# MotorControl-v1.net
KiCad netlist of a schematic drawn in EAGLE
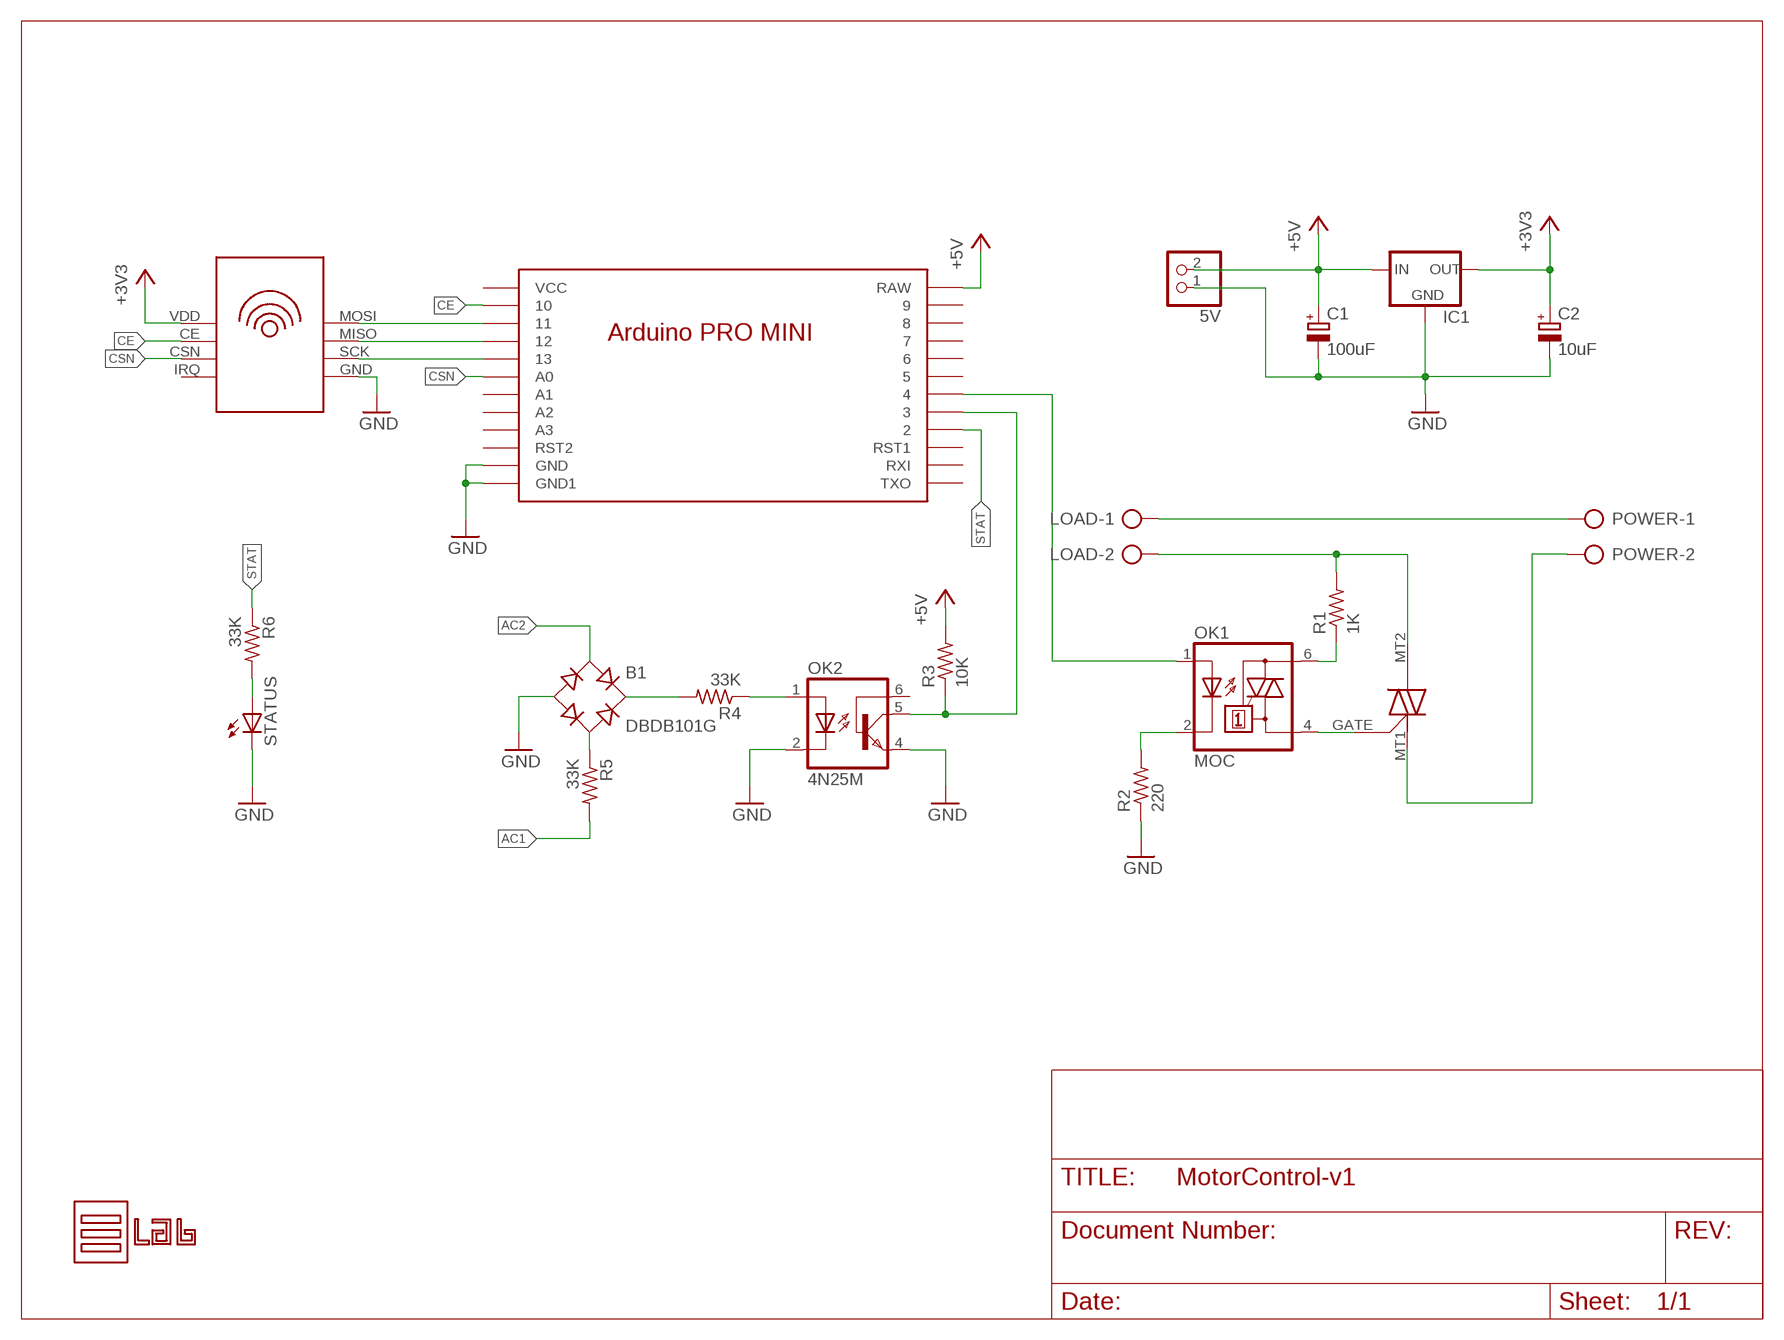
[diagram p0: schematic, sheet 1]

(export (version "E")
  (design (tool "Eeschema 10.0.6"))
  (components
    (comp (ref "5V")
      (value "PINHD-1X2")
      (footprint "eagle-import:1X02")
      (libsource (lib "eagle-import") (part "PINHD-1X2"))
    )
    (comp (ref "B1")
      (value "DBDB101G")
      (footprint "eagle-import:DB")
      (libsource (lib "eagle-import") (part "DB?GDB101"))
    )
    (comp (ref "C1")
      (value "100uF")
      (footprint "eagle-import:E2-5")
      (libsource (lib "eagle-import") (part "CPOL-EUE2-5"))
    )
    (comp (ref "C2")
      (value "10uF")
      (footprint "eagle-import:E2-5")
      (libsource (lib "eagle-import") (part "CPOL-EUE2-5"))
    )
    (comp (ref "IC1")
      (value "78LXX")
      (footprint "eagle-import:78LXX")
      (libsource (lib "eagle-import") (part "78LXX"))
    )
    (comp (ref "J1")
      (value "MAC12")
      (footprint "eagle-import:MAC12")
      (libsource (lib "eagle-import") (part "MAC12"))
    )
    (comp (ref "LOAD")
      (value "AK300/2")
      (footprint "eagle-import:AK300_2")
      (libsource (lib "eagle-import") (part "AK300/2"))
    )
    (comp (ref "OK1")
      (value "MOC")
      (footprint "eagle-import:DIL06")
      (fields (field (name "MF") "FAIRCHILD SEMICONDUCTOR") (field (name "MPN") "MOC3041M"))
      (libsource (lib "eagle-import") (part "MOC3041M"))
    )
    (comp (ref "OK2")
      (value "4N25M")
      (footprint "eagle-import:DIL06")
      (fields (field (name "MPN") "4N25-M"))
      (libsource (lib "eagle-import") (part "4N?M25"))
    )
    (comp (ref "POWER")
      (value "AK300/2")
      (footprint "eagle-import:AK300_2")
      (libsource (lib "eagle-import") (part "AK300/2"))
    )
    (comp (ref "R1")
      (value "1K")
      (footprint "eagle-import:0204_7")
      (libsource (lib "eagle-import") (part "R-US_0204/7"))
    )
    (comp (ref "R2")
      (value "220")
      (footprint "eagle-import:0204_7")
      (libsource (lib "eagle-import") (part "R-US_0204/7"))
    )
    (comp (ref "R3")
      (value "10K")
      (footprint "eagle-import:0204_7")
      (libsource (lib "eagle-import") (part "R-US_0204/7"))
    )
    (comp (ref "R4")
      (value "33K")
      (footprint "eagle-import:0204_7")
      (libsource (lib "eagle-import") (part "R-US_0204/7"))
    )
    (comp (ref "R5")
      (value "33K")
      (footprint "eagle-import:0204_7")
      (libsource (lib "eagle-import") (part "R-US_0204/7"))
    )
    (comp (ref "R6")
      (value "33K")
      (footprint "eagle-import:0204_7")
      (libsource (lib "eagle-import") (part "R-US_0204/7"))
    )
    (comp (ref "STATUS")
      (value "LED3MM")
      (footprint "eagle-import:LED3MM")
      (libsource (lib "eagle-import") (part "LED3MM"))
    )
    (comp (ref "U$1")
      (value "NANO")
      (footprint "eagle-import:NANO")
      (libsource (lib "eagle-import") (part "NANO"))
    )
    (comp (ref "U$2")
      (value "NRF24L01")
      (footprint "eagle-import:NRF24L01")
      (libsource (lib "eagle-import") (part "NRF24L01"))
    )
    (comp (ref "U$3")
      (value "LOGO")
      (footprint "eagle-import:LOGO")
      (libsource (lib "eagle-import") (part "LOGO"))
    )
  )
  (nets
    (net (code "1") (name "+3V3") (class "Default")
      (node (ref "C2") (pin "+") (pinfunction "+_+") (pintype "passive"))
      (node (ref "IC1") (pin "OUT") (pinfunction "OUT_OUT") (pintype "passive"))
      (node (ref "U$2") (pin "VDD") (pinfunction "VDD_VDD") (pintype "bidirectional"))
    )
    (net (code "2") (name "+5V") (class "Default")
      (node (ref "5V") (pin "2") (pinfunction "2_2") (pintype "passive"))
      (node (ref "C1") (pin "+") (pinfunction "+_+") (pintype "passive"))
      (node (ref "IC1") (pin "IN") (pinfunction "IN_IN") (pintype "input"))
      (node (ref "R3") (pin "2") (pinfunction "2_2") (pintype "passive"))
      (node (ref "U$1") (pin "RAW") (pinfunction "RAW_RAW") (pintype "bidirectional"))
    )
    (net (code "3") (name "AC1") (class "Default")
      (node (ref "J1") (pin "MT1") (pinfunction "MT1_MT1") (pintype "bidirectional"))
      (node (ref "POWER") (pin "2") (pinfunction "KL_2") (pintype "passive"))
      (node (ref "R5") (pin "2") (pinfunction "2_2") (pintype "passive"))
    )
    (net (code "4") (name "AC2") (class "Default")
      (node (ref "B1") (pin "AC1") (pinfunction "AC1_AC1") (pintype "passive"))
      (node (ref "LOAD") (pin "1") (pinfunction "KL_1") (pintype "passive"))
      (node (ref "POWER") (pin "1") (pinfunction "KL_1") (pintype "passive"))
    )
    (net (code "5") (name "CE") (class "Default")
      (node (ref "U$1") (pin "10") (pinfunction "10_10") (pintype "bidirectional"))
      (node (ref "U$2") (pin "CE") (pinfunction "CE_CE") (pintype "bidirectional"))
    )
    (net (code "6") (name "CSN") (class "Default")
      (node (ref "U$1") (pin "A0") (pinfunction "A0_A0") (pintype "bidirectional"))
      (node (ref "U$2") (pin "CSN") (pinfunction "CSN_CSN") (pintype "bidirectional"))
    )
    (net (code "7") (name "GND") (class "Default")
      (node (ref "5V") (pin "1") (pinfunction "1_1") (pintype "passive"))
      (node (ref "B1") (pin "-") (pinfunction "-_-") (pintype "passive"))
      (node (ref "C1") (pin "-") (pinfunction "-_-") (pintype "passive"))
      (node (ref "C2") (pin "-") (pinfunction "-_-") (pintype "passive"))
      (node (ref "IC1") (pin "GND") (pinfunction "GND_GND") (pintype "input"))
      (node (ref "OK2") (pin "2") (pinfunction "C_2") (pintype "passive"))
      (node (ref "OK2") (pin "4") (pinfunction "EMI_4") (pintype "passive"))
      (node (ref "R2") (pin "1") (pinfunction "1_1") (pintype "passive"))
      (node (ref "STATUS") (pin "K") (pinfunction "C_K") (pintype "passive"))
      (node (ref "U$1") (pin "GND1") (pinfunction "GND_GND1") (pintype "bidirectional"))
      (node (ref "U$1") (pin "GND2") (pinfunction "GND1_GND2") (pintype "power_in"))
      (node (ref "U$2") (pin "GND") (pinfunction "GND_GND") (pintype "bidirectional"))
    )
    (net (code "8") (name "Net-(B1-Pad+)") (class "Default")
      (node (ref "B1") (pin "+") (pinfunction "+_+") (pintype "passive"))
      (node (ref "R4") (pin "2") (pinfunction "2_2") (pintype "passive"))
    )
    (net (code "9") (name "Net-(B1-PadAC2)") (class "Default")
      (node (ref "B1") (pin "AC2") (pinfunction "AC2_AC2") (pintype "passive"))
      (node (ref "R5") (pin "1") (pinfunction "1_1") (pintype "passive"))
    )
    (net (code "10") (name "Net-(LOADB-KL)") (class "Default")
      (node (ref "J1") (pin "MT2") (pinfunction "MT2_MT2") (pintype "bidirectional"))
      (node (ref "LOAD") (pin "2") (pinfunction "KL_2") (pintype "passive"))
      (node (ref "R1") (pin "2") (pinfunction "2_2") (pintype "passive"))
    )
    (net (code "11") (name "Net-(OK1-A)") (class "Default")
      (node (ref "OK1") (pin "1") (pinfunction "A_1") (pintype "passive"))
      (node (ref "U$1") (pin "4") (pinfunction "4_4") (pintype "bidirectional"))
    )
    (net (code "12") (name "Net-(OK1-A1)") (class "Default")
      (node (ref "J1") (pin "GATE") (pinfunction "GATE_GATE") (pintype "bidirectional"))
      (node (ref "OK1") (pin "4") (pinfunction "A1_4") (pintype "passive"))
    )
    (net (code "13") (name "Net-(OK1-A2)") (class "Default")
      (node (ref "OK1") (pin "6") (pinfunction "A2_6") (pintype "passive"))
      (node (ref "R1") (pin "1") (pinfunction "1_1") (pintype "passive"))
    )
    (net (code "14") (name "Net-(OK1-C)") (class "Default")
      (node (ref "OK1") (pin "2") (pinfunction "C_2") (pintype "passive"))
      (node (ref "R2") (pin "2") (pinfunction "2_2") (pintype "passive"))
    )
    (net (code "15") (name "Net-(OK2-A)") (class "Default")
      (node (ref "OK2") (pin "1") (pinfunction "A_1") (pintype "passive"))
      (node (ref "R4") (pin "1") (pinfunction "1_1") (pintype "passive"))
    )
    (net (code "16") (name "Net-(OK2-COL)") (class "Default")
      (node (ref "OK2") (pin "5") (pinfunction "COL_5") (pintype "passive"))
      (node (ref "R3") (pin "1") (pinfunction "1_1") (pintype "passive"))
      (node (ref "U$1") (pin "3") (pinfunction "3_3") (pintype "bidirectional"))
    )
    (net (code "17") (name "Net-(R6-Pad2)") (class "Default")
      (node (ref "R6") (pin "2") (pinfunction "2_2") (pintype "passive"))
      (node (ref "STATUS") (pin "A") (pinfunction "A_A") (pintype "passive"))
    )
    (net (code "18") (name "Net-(U$1-Pad11)") (class "Default")
      (node (ref "U$1") (pin "11") (pinfunction "11_11") (pintype "bidirectional"))
      (node (ref "U$2") (pin "MOSI") (pinfunction "MOSI_MOSI") (pintype "bidirectional"))
    )
    (net (code "19") (name "Net-(U$1-Pad12)") (class "Default")
      (node (ref "U$1") (pin "12") (pinfunction "12_12") (pintype "bidirectional"))
      (node (ref "U$2") (pin "MISO") (pinfunction "MISO_MISO") (pintype "bidirectional"))
    )
    (net (code "20") (name "Net-(U$1-Pad13)") (class "Default")
      (node (ref "U$1") (pin "13") (pinfunction "13_13") (pintype "bidirectional"))
      (node (ref "U$2") (pin "SCK") (pinfunction "SCK_SCK") (pintype "bidirectional"))
    )
    (net (code "21") (name "STAT") (class "Default")
      (node (ref "R6") (pin "1") (pinfunction "1_1") (pintype "passive"))
      (node (ref "U$1") (pin "2") (pinfunction "2_2") (pintype "bidirectional"))
    )
    (net (code "22") (name "unconnected-(OK2-BAS-Pad6)") (class "Default")
      (node (ref "OK2") (pin "6") (pinfunction "BAS_6") (pintype "passive"))
    )
    (net (code "23") (name "unconnected-(U$1-Pad5)") (class "Default")
      (node (ref "U$1") (pin "5") (pinfunction "5_5") (pintype "bidirectional"))
    )
    (net (code "24") (name "unconnected-(U$1-Pad6)") (class "Default")
      (node (ref "U$1") (pin "6") (pinfunction "6_6") (pintype "bidirectional"))
    )
    (net (code "25") (name "unconnected-(U$1-Pad7)") (class "Default")
      (node (ref "U$1") (pin "7") (pinfunction "7_7") (pintype "bidirectional"))
    )
    (net (code "26") (name "unconnected-(U$1-Pad8)") (class "Default")
      (node (ref "U$1") (pin "8") (pinfunction "8_8") (pintype "bidirectional"))
    )
    (net (code "27") (name "unconnected-(U$1-Pad9)") (class "Default")
      (node (ref "U$1") (pin "9") (pinfunction "9_9") (pintype "bidirectional"))
    )
    (net (code "28") (name "unconnected-(U$1-PadA1)") (class "Default")
      (node (ref "U$1") (pin "A1") (pinfunction "A1_A1") (pintype "bidirectional"))
    )
    (net (code "29") (name "unconnected-(U$1-PadA2)") (class "Default")
      (node (ref "U$1") (pin "A2") (pinfunction "A2_A2") (pintype "bidirectional"))
    )
    (net (code "30") (name "unconnected-(U$1-PadA3)") (class "Default")
      (node (ref "U$1") (pin "A3") (pinfunction "A3_A3") (pintype "bidirectional"))
    )
    (net (code "31") (name "unconnected-(U$1-PadRST1)") (class "Default")
      (node (ref "U$1") (pin "RST1") (pinfunction "RST1_RST1") (pintype "bidirectional"))
    )
    (net (code "32") (name "unconnected-(U$1-PadRST2)") (class "Default")
      (node (ref "U$1") (pin "RST2") (pinfunction "RST2_RST2") (pintype "bidirectional"))
    )
    (net (code "33") (name "unconnected-(U$1-PadRXI)") (class "Default")
      (node (ref "U$1") (pin "RXI") (pinfunction "RXI_RXI") (pintype "bidirectional"))
    )
    (net (code "34") (name "unconnected-(U$1-PadTXO)") (class "Default")
      (node (ref "U$1") (pin "TXO") (pinfunction "TXO_TXO") (pintype "bidirectional"))
    )
    (net (code "35") (name "unconnected-(U$1-PadVCC)") (class "Default")
      (node (ref "U$1") (pin "VCC") (pinfunction "VCC_VCC") (pintype "bidirectional"))
    )
    (net (code "36") (name "unconnected-(U$2-PadIRQ)") (class "Default")
      (node (ref "U$2") (pin "IRQ") (pinfunction "IRQ_IRQ") (pintype "bidirectional"))
    )
  )
)
